# Esquematico.net
KiCad netlist of a schematic drawn in Altium Designer
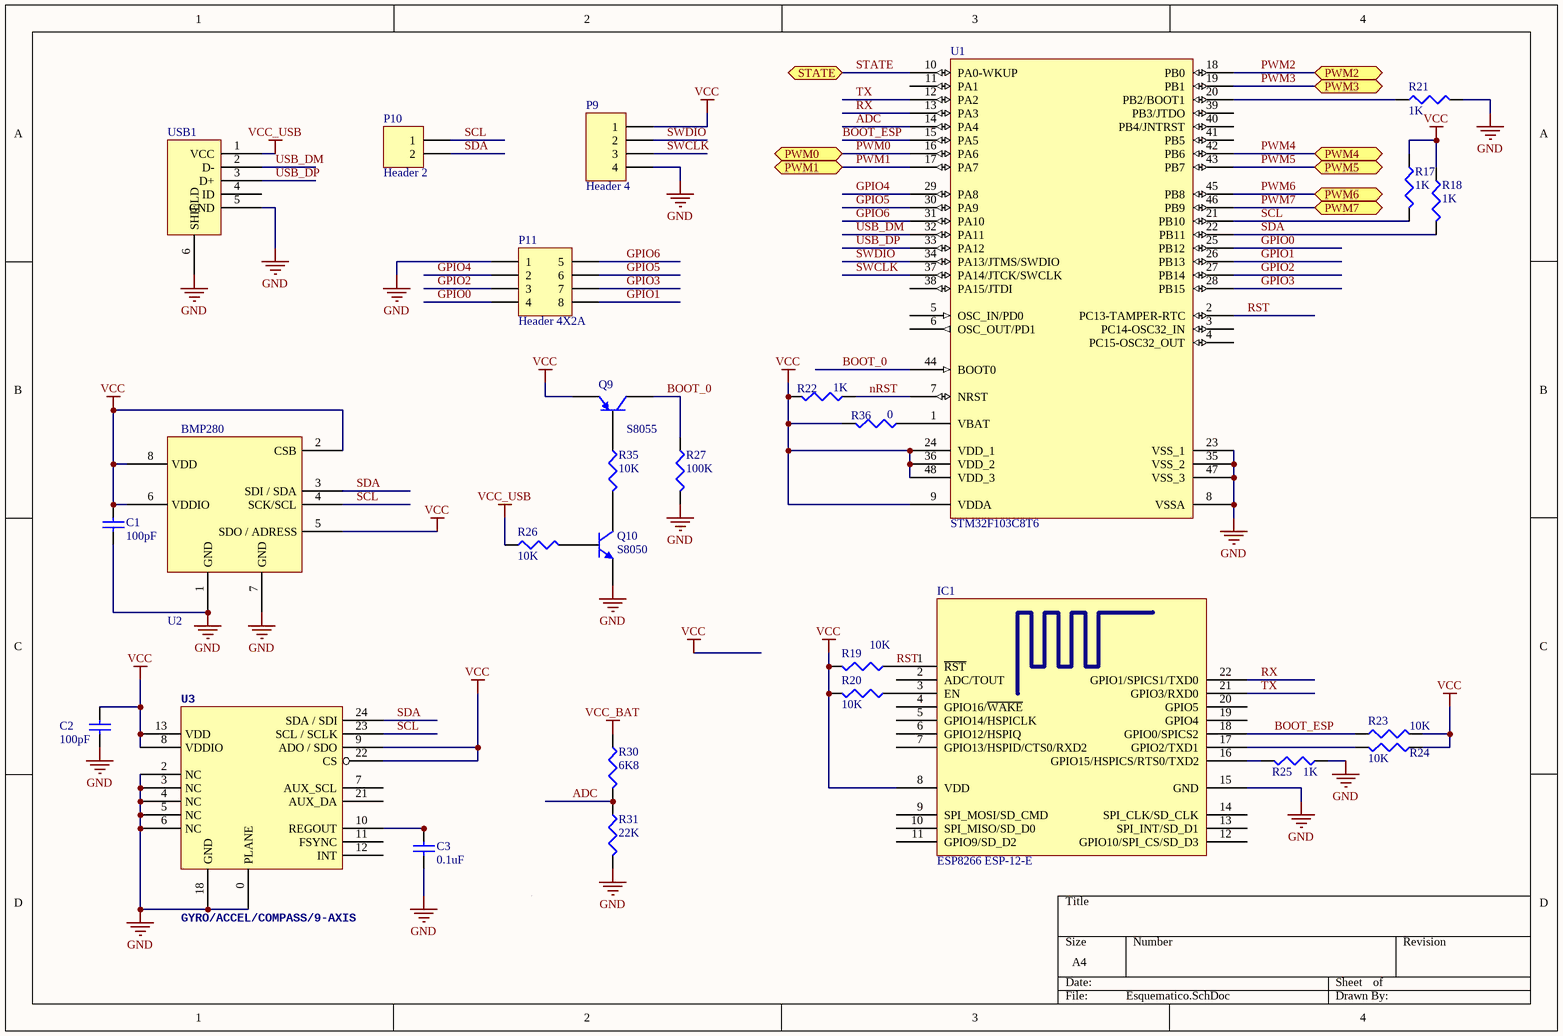
[diagram p0: Esquematico.SchDoc]

(export (version "E")
  (design (tool "Eeschema 10.0.6"))
  (components
    (comp (ref "C1")
      (value "100pF")
      (footprint "Miscellaneous Devices:6-0805_L")
      (description "Capacitor")
      (fields (field (name "Comment") "Cap") (field (name "PUBLISHER") "Altium Limited"))
      (libsource (lib "Miscellaneous Devices") (part "Cap"))
    )
    (comp (ref "C2")
      (value "100pF")
      (footprint "C1206")
      (description "Capacitor")
      (fields (field (name "Comment") "Cap") (field (name "PUBLISHER") "Altium Limited"))
      (libsource (lib "Miscellaneous Devices") (part "Cap"))
    )
    (comp (ref "C3")
      (value "0.1uF")
      (footprint "C1206")
      (description "Capacitor")
      (fields (field (name "Comment") "Cap") (field (name "PUBLISHER") "Altium Limited"))
      (libsource (lib "Miscellaneous Devices") (part "Cap"))
    )
    (comp (ref "IC1")
      (value "ESP8266 ESP-12-E")
      (footprint "ESP8266:ESP8266 ESP-12-E B")
      (libsource (lib "ESP8266") (part "ESP8266 ESP-12-E"))
    )
    (comp (ref "P9")
      (value "Header 4")
      (footprint "HDR1X4")
      (description "Header, 4-Pin")
      (fields (field (name "PUBLISHER") "Altium Limited"))
      (libsource (lib "Miscellaneous Connectors") (part "Header 4"))
    )
    (comp (ref "P10")
      (value "Header 2")
      (footprint "HDR1X2")
      (description "Header, 2-Pin")
      (fields (field (name "PUBLISHER") "Altium Limited"))
      (libsource (lib "Miscellaneous Connectors") (part "Header 2"))
    )
    (comp (ref "P11")
      (value "Header 4X2A")
      (footprint "HDR2X4_CEN")
      (description "Header, 4-Pin, Dual row")
      (fields (field (name "PUBLISHER") "Altium Limited"))
      (libsource (lib "Miscellaneous Connectors") (part "Header 4X2A"))
    )
    (comp (ref "Q9")
      (value "S8055")
      (footprint "SOT23-3")
      (description "PNP SMD General Purpose Amplifier")
      (fields (field (name "PUBLISHER") "Altium Limited"))
      (libsource (lib "Libreria General") (part "S8055"))
    )
    (comp (ref "Q10")
      (value "S8050")
      (footprint "SOT23-3")
      (description "NPN SMD General Purpose Amplifier")
      (fields (field (name "PUBLISHER") "Altium Limited"))
      (libsource (lib "Libreria General") (part "S8050"))
    )
    (comp (ref "R17")
      (value "1K")
      (footprint "C1206")
      (description "Resistor")
      (fields (field (name "Comment") "Res3") (field (name "PUBLISHER") "Altium Limited"))
      (libsource (lib "Miscellaneous Devices") (part "Res3"))
    )
    (comp (ref "R18")
      (value "1K")
      (footprint "C1206")
      (description "Resistor")
      (fields (field (name "Comment") "Res3") (field (name "PUBLISHER") "Altium Limited"))
      (libsource (lib "Miscellaneous Devices") (part "Res3"))
    )
    (comp (ref "R19")
      (value "10K")
      (footprint "6-0805_N")
      (description "Resistor")
      (fields (field (name "Comment") "Res3") (field (name "PUBLISHER") "Altium Limited"))
      (libsource (lib "Miscellaneous Devices") (part "Res3"))
    )
    (comp (ref "R20")
      (value "10K")
      (footprint "6-0805_N")
      (description "Resistor")
      (fields (field (name "Comment") "Res3") (field (name "PUBLISHER") "Altium Limited"))
      (libsource (lib "Miscellaneous Devices") (part "Res3"))
    )
    (comp (ref "R21")
      (value "1K")
      (footprint "C1206")
      (description "Resistor")
      (fields (field (name "Comment") "Res3") (field (name "PUBLISHER") "Altium Limited"))
      (libsource (lib "Miscellaneous Devices") (part "Res3"))
    )
    (comp (ref "R22")
      (value "1K")
      (footprint "6-0805_N")
      (description "Resistor")
      (fields (field (name "Comment") "Res3") (field (name "PUBLISHER") "Altium Limited"))
      (libsource (lib "Miscellaneous Devices") (part "Res3"))
    )
    (comp (ref "R23")
      (value "10K")
      (footprint "6-0805_N")
      (description "Resistor")
      (fields (field (name "Comment") "Res3") (field (name "PUBLISHER") "Altium Limited"))
      (libsource (lib "Miscellaneous Devices") (part "Res3"))
    )
    (comp (ref "R24")
      (value "10K")
      (footprint "6-0805_N")
      (description "Resistor")
      (fields (field (name "Comment") "Res3") (field (name "PUBLISHER") "Altium Limited"))
      (libsource (lib "Miscellaneous Devices") (part "Res3"))
    )
    (comp (ref "R25")
      (value "1K")
      (footprint "6-0805_N")
      (description "Resistor")
      (fields (field (name "Comment") "Res3") (field (name "PUBLISHER") "Altium Limited"))
      (libsource (lib "Miscellaneous Devices") (part "Res3"))
    )
    (comp (ref "R26")
      (value "10K")
      (footprint "6-0805_N")
      (description "Resistor")
      (fields (field (name "Comment") "Res3") (field (name "PUBLISHER") "Altium Limited"))
      (libsource (lib "Miscellaneous Devices") (part "Res3"))
    )
    (comp (ref "R27")
      (value "100K")
      (footprint "6-0805_N")
      (description "Resistor")
      (fields (field (name "Comment") "Res3") (field (name "PUBLISHER") "Altium Limited"))
      (libsource (lib "Miscellaneous Devices") (part "Res3"))
    )
    (comp (ref "R30")
      (value "6K8")
      (footprint "6-0805_N")
      (description "Resistor")
      (fields (field (name "Comment") "Res3") (field (name "PUBLISHER") "Altium Limited"))
      (libsource (lib "Miscellaneous Devices") (part "Res3"))
    )
    (comp (ref "R31")
      (value "22K")
      (footprint "6-0805_N")
      (description "Resistor")
      (fields (field (name "Comment") "Res3") (field (name "PUBLISHER") "Altium Limited"))
      (libsource (lib "Miscellaneous Devices") (part "Res3"))
    )
    (comp (ref "R35")
      (value "10K")
      (footprint "6-0805_N")
      (description "Resistor")
      (fields (field (name "Comment") "Res3") (field (name "PUBLISHER") "Altium Limited"))
      (libsource (lib "Miscellaneous Devices") (part "Res3"))
    )
    (comp (ref "R36")
      (value "0")
      (footprint "6-0805_N")
      (description "Resistor")
      (fields (field (name "Comment") "Res3") (field (name "PUBLISHER") "Altium Limited"))
      (libsource (lib "Miscellaneous Devices") (part "Res3"))
    )
    (comp (ref "U1")
      (value "STM32F103C8T6")
      (footprint "LQFP48_N")
      (description "STM32 ARM-based 32-bit MCU with 64 Kbytes Flash, 48-pin LQFP, Industrial Temperature")
      (fields (field (name "PUBLISHER") "Altium Limited"))
      (libsource (lib "ST Microcontroller 32-Bit STM32") (part "STM32F103C8T6"))
    )
    (comp (ref "U2")
      (value "BMP280")
      (footprint "LGA-8_BMP280(Primary)")
      (description "Barometro")
      (libsource (lib "BMP280") (part "BMP280"))
    )
    (comp (ref "U3")
      (value "GYRO/ACCEL/COMPASS/9-AXIS")
      (footprint "QFN-24/3MM")
      (libsource (lib "MPU-9250") (part "MPU-9250"))
    )
    (comp (ref "USB1")
      (value "Micro_USB")
      (footprint "Micro USB")
      (libsource (lib "Libreria General") (part "Micro_USB"))
    )
  )
  (nets
    (net (code "1") (name "/ADC") (class "Default")
      (node (ref "R30") (pin "2") (pinfunction "2_2") (pintype "passive"))
      (node (ref "R31") (pin "1") (pinfunction "1_1") (pintype "passive"))
      (node (ref "U1") (pin "14") (pinfunction "PA4_14") (pintype "bidirectional"))
    )
    (net (code "2") (name "/BOOT_0") (class "Default")
      (node (ref "Q9") (pin "3") (pinfunction "C_3") (pintype "passive"))
      (node (ref "R27") (pin "1") (pinfunction "1_1") (pintype "passive"))
      (node (ref "U1") (pin "44") (pinfunction "BOOT0_44") (pintype "input"))
    )
    (net (code "3") (name "/BOOT_ESP") (class "Default")
      (node (ref "IC1") (pin "18") (pinfunction "GPIO0/SPICS2_18") (pintype "passive"))
      (node (ref "R23") (pin "1") (pinfunction "1_1") (pintype "passive"))
      (node (ref "U1") (pin "15") (pinfunction "PA5_15") (pintype "bidirectional"))
    )
    (net (code "4") (name "/GPIO0") (class "Default")
      (node (ref "P11") (pin "4") (pinfunction "4_4") (pintype "passive"))
      (node (ref "U1") (pin "25") (pinfunction "PB12_25") (pintype "bidirectional"))
    )
    (net (code "5") (name "/GPIO1") (class "Default")
      (node (ref "P11") (pin "8") (pinfunction "8_8") (pintype "passive"))
      (node (ref "U1") (pin "26") (pinfunction "PB13_26") (pintype "bidirectional"))
    )
    (net (code "6") (name "/GPIO2") (class "Default")
      (node (ref "P11") (pin "3") (pinfunction "3_3") (pintype "passive"))
      (node (ref "U1") (pin "27") (pinfunction "PB14_27") (pintype "bidirectional"))
    )
    (net (code "7") (name "/GPIO3") (class "Default")
      (node (ref "P11") (pin "7") (pinfunction "7_7") (pintype "passive"))
      (node (ref "U1") (pin "28") (pinfunction "PB15_28") (pintype "bidirectional"))
    )
    (net (code "8") (name "/GPIO4") (class "Default")
      (node (ref "P11") (pin "2") (pinfunction "2_2") (pintype "passive"))
      (node (ref "U1") (pin "29") (pinfunction "PA8_29") (pintype "bidirectional"))
    )
    (net (code "9") (name "/GPIO5") (class "Default")
      (node (ref "P11") (pin "6") (pinfunction "6_6") (pintype "passive"))
      (node (ref "U1") (pin "30") (pinfunction "PA9_30") (pintype "bidirectional"))
    )
    (net (code "10") (name "/GPIO6") (class "Default")
      (node (ref "P11") (pin "5") (pinfunction "5_5") (pintype "passive"))
      (node (ref "U1") (pin "31") (pinfunction "PA10_31") (pintype "bidirectional"))
    )
    (net (code "11") (name "/PWM0") (class "Default")
      (node (ref "U1") (pin "16") (pinfunction "PA6_16") (pintype "bidirectional"))
    )
    (net (code "12") (name "/PWM1") (class "Default")
      (node (ref "U1") (pin "17") (pinfunction "PA7_17") (pintype "bidirectional"))
    )
    (net (code "13") (name "/PWM2") (class "Default")
      (node (ref "U1") (pin "18") (pinfunction "PB0_18") (pintype "bidirectional"))
    )
    (net (code "14") (name "/PWM3") (class "Default")
      (node (ref "U1") (pin "19") (pinfunction "PB1_19") (pintype "bidirectional"))
    )
    (net (code "15") (name "/PWM4") (class "Default")
      (node (ref "U1") (pin "42") (pinfunction "PB6_42") (pintype "bidirectional"))
    )
    (net (code "16") (name "/PWM5") (class "Default")
      (node (ref "U1") (pin "43") (pinfunction "PB7_43") (pintype "bidirectional"))
    )
    (net (code "17") (name "/PWM6") (class "Default")
      (node (ref "U1") (pin "45") (pinfunction "PB8_45") (pintype "bidirectional"))
    )
    (net (code "18") (name "/PWM7") (class "Default")
      (node (ref "U1") (pin "46") (pinfunction "PB9_46") (pintype "bidirectional"))
    )
    (net (code "19") (name "/RST") (class "Default")
      (node (ref "IC1") (pin "1") (pinfunction "~{RST}_1") (pintype "passive"))
      (node (ref "R19") (pin "1") (pinfunction "1_1") (pintype "passive"))
      (node (ref "U1") (pin "2") (pinfunction "PC13-TAMPER-RTC_2") (pintype "bidirectional"))
    )
    (net (code "20") (name "/RX") (class "Default")
      (node (ref "IC1") (pin "22") (pinfunction "GPIO1/SPICS1/TXD0_22") (pintype "passive"))
      (node (ref "U1") (pin "13") (pinfunction "PA3_13") (pintype "bidirectional"))
    )
    (net (code "21") (name "/SCL") (class "Default")
      (node (ref "P10") (pin "1") (pinfunction "1_1") (pintype "passive"))
      (node (ref "R17") (pin "2") (pinfunction "2_2") (pintype "passive"))
      (node (ref "U1") (pin "21") (pinfunction "PB10_21") (pintype "bidirectional"))
      (node (ref "U2") (pin "4") (pinfunction "SCK/SCL_4") (pintype "passive"))
      (node (ref "U3") (pin "23") (pinfunction "SCL_/_SCLK_23") (pintype "passive"))
    )
    (net (code "22") (name "/SDA") (class "Default")
      (node (ref "P10") (pin "2") (pinfunction "2_2") (pintype "passive"))
      (node (ref "R18") (pin "2") (pinfunction "2_2") (pintype "passive"))
      (node (ref "U1") (pin "22") (pinfunction "PB11_22") (pintype "bidirectional"))
      (node (ref "U2") (pin "3") (pinfunction "SDI_/_SDA_3") (pintype "passive"))
      (node (ref "U3") (pin "24") (pinfunction "SDA_/_SDI_24") (pintype "passive"))
    )
    (net (code "23") (name "/STATE") (class "Default")
      (node (ref "U1") (pin "10") (pinfunction "PA0-WKUP_10") (pintype "bidirectional"))
    )
    (net (code "24") (name "/SWCLK") (class "Default")
      (node (ref "P9") (pin "3") (pinfunction "3_3") (pintype "passive"))
      (node (ref "U1") (pin "37") (pinfunction "PA14/JTCK/SWCLK_37") (pintype "bidirectional"))
    )
    (net (code "25") (name "/SWDIO") (class "Default")
      (node (ref "P9") (pin "2") (pinfunction "2_2") (pintype "passive"))
      (node (ref "U1") (pin "34") (pinfunction "PA13/JTMS/SWDIO_34") (pintype "bidirectional"))
    )
    (net (code "26") (name "/TX") (class "Default")
      (node (ref "IC1") (pin "21") (pinfunction "GPIO3/RXD0_21") (pintype "passive"))
      (node (ref "U1") (pin "12") (pinfunction "PA2_12") (pintype "bidirectional"))
    )
    (net (code "27") (name "/USB_DM") (class "Default")
      (node (ref "U1") (pin "32") (pinfunction "PA11_32") (pintype "bidirectional"))
      (node (ref "USB1") (pin "2") (pinfunction "D-_2") (pintype "passive"))
    )
    (net (code "28") (name "/USB_DP") (class "Default")
      (node (ref "U1") (pin "33") (pinfunction "PA12_33") (pintype "bidirectional"))
      (node (ref "USB1") (pin "3") (pinfunction "D+_3") (pintype "passive"))
    )
    (net (code "29") (name "/nRST") (class "Default")
      (node (ref "R22") (pin "1") (pinfunction "1_1") (pintype "passive"))
      (node (ref "U1") (pin "7") (pinfunction "NRST_7") (pintype "bidirectional"))
    )
    (net (code "30") (name "GND") (class "Default")
      (node (ref "C1") (pin "1") (pinfunction "1_1") (pintype "passive"))
      (node (ref "C2") (pin "1") (pinfunction "1_1") (pintype "passive"))
      (node (ref "C3") (pin "1") (pinfunction "1_1") (pintype "passive"))
      (node (ref "IC1") (pin "15") (pinfunction "GND_15") (pintype "passive"))
      (node (ref "P11") (pin "1") (pinfunction "1_1") (pintype "passive"))
      (node (ref "P9") (pin "4") (pinfunction "4_4") (pintype "passive"))
      (node (ref "Q10") (pin "2") (pinfunction "E_2") (pintype "passive"))
      (node (ref "R21") (pin "2") (pinfunction "2_2") (pintype "passive"))
      (node (ref "R25") (pin "1") (pinfunction "1_1") (pintype "passive"))
      (node (ref "R27") (pin "2") (pinfunction "2_2") (pintype "passive"))
      (node (ref "R31") (pin "2") (pinfunction "2_2") (pintype "passive"))
      (node (ref "U1") (pin "23") (pinfunction "VSS_1_23") (pintype "power_in"))
      (node (ref "U1") (pin "35") (pinfunction "VSS_2_35") (pintype "power_in"))
      (node (ref "U1") (pin "47") (pinfunction "VSS_3_47") (pintype "power_in"))
      (node (ref "U1") (pin "8") (pinfunction "VSSA_8") (pintype "power_in"))
      (node (ref "U2") (pin "1") (pinfunction "GND_1") (pintype "passive"))
      (node (ref "U2") (pin "7") (pinfunction "GND_7") (pintype "passive"))
      (node (ref "U3") (pin "0") (pinfunction "PLANE_0") (pintype "passive"))
      (node (ref "U3") (pin "18") (pinfunction "GND_18") (pintype "passive"))
      (node (ref "U3") (pin "2") (pinfunction "NC_2") (pintype "passive"))
      (node (ref "U3") (pin "3") (pinfunction "NC_3") (pintype "passive"))
      (node (ref "U3") (pin "4") (pinfunction "NC_4") (pintype "passive"))
      (node (ref "U3") (pin "5") (pinfunction "NC_5") (pintype "passive"))
      (node (ref "U3") (pin "6") (pinfunction "NC_6") (pintype "passive"))
      (node (ref "USB1") (pin "5") (pinfunction "GND_5") (pintype "passive"))
      (node (ref "USB1") (pin "6") (pinfunction "SHIELD_6") (pintype "passive"))
    )
    (net (code "31") (name "Net-(IC1-EN)") (class "Default")
      (node (ref "IC1") (pin "3") (pinfunction "EN_3") (pintype "passive"))
      (node (ref "R20") (pin "1") (pinfunction "1_1") (pintype "passive"))
    )
    (net (code "32") (name "Net-(IC1-GPIO2{slash}TXD1)") (class "Default")
      (node (ref "IC1") (pin "17") (pinfunction "GPIO2/TXD1_17") (pintype "passive"))
      (node (ref "R24") (pin "2") (pinfunction "2_2") (pintype "passive"))
    )
    (net (code "33") (name "Net-(IC1-GPIO15{slash}HSPICS{slash}RTS0{slash}TXD2)") (class "Default")
      (node (ref "IC1") (pin "16") (pinfunction "GPIO15/HSPICS/RTS0/TXD2_16") (pintype "passive"))
      (node (ref "R25") (pin "2") (pinfunction "2_2") (pintype "passive"))
    )
    (net (code "34") (name "Net-(Q9-B)") (class "Default")
      (node (ref "Q9") (pin "1") (pinfunction "B_1") (pintype "passive"))
      (node (ref "R35") (pin "1") (pinfunction "1_1") (pintype "passive"))
    )
    (net (code "35") (name "Net-(Q10-B)") (class "Default")
      (node (ref "Q10") (pin "1") (pinfunction "B_1") (pintype "passive"))
      (node (ref "R26") (pin "2") (pinfunction "2_2") (pintype "passive"))
    )
    (net (code "36") (name "Net-(Q10-C)") (class "Default")
      (node (ref "Q10") (pin "3") (pinfunction "C_3") (pintype "passive"))
      (node (ref "R35") (pin "2") (pinfunction "2_2") (pintype "passive"))
    )
    (net (code "37") (name "Net-(U1-PB2{slash}BOOT1)") (class "Default")
      (node (ref "R21") (pin "1") (pinfunction "1_1") (pintype "passive"))
      (node (ref "U1") (pin "20") (pinfunction "PB2/BOOT1_20") (pintype "bidirectional"))
    )
    (net (code "38") (name "Net-(U1-VBAT)") (class "Default")
      (node (ref "R36") (pin "1") (pinfunction "1_1") (pintype "passive"))
      (node (ref "U1") (pin "1") (pinfunction "VBAT_1") (pintype "power_in"))
    )
    (net (code "39") (name "Net-(U3-REGOUT)") (class "Default")
      (node (ref "C3") (pin "2") (pinfunction "2_2") (pintype "passive"))
      (node (ref "U3") (pin "10") (pinfunction "REGOUT_10") (pintype "passive"))
    )
    (net (code "40") (name "VCC") (class "Default")
      (node (ref "C1") (pin "2") (pinfunction "2_2") (pintype "passive"))
      (node (ref "C2") (pin "2") (pinfunction "2_2") (pintype "passive"))
      (node (ref "IC1") (pin "8") (pinfunction "VDD_8") (pintype "passive"))
      (node (ref "P9") (pin "1") (pinfunction "1_1") (pintype "passive"))
      (node (ref "Q9") (pin "2") (pinfunction "E_2") (pintype "passive"))
      (node (ref "R17") (pin "1") (pinfunction "1_1") (pintype "passive"))
      (node (ref "R18") (pin "1") (pinfunction "1_1") (pintype "passive"))
      (node (ref "R19") (pin "2") (pinfunction "2_2") (pintype "passive"))
      (node (ref "R20") (pin "2") (pinfunction "2_2") (pintype "passive"))
      (node (ref "R22") (pin "2") (pinfunction "2_2") (pintype "passive"))
      (node (ref "R23") (pin "2") (pinfunction "2_2") (pintype "passive"))
      (node (ref "R24") (pin "1") (pinfunction "1_1") (pintype "passive"))
      (node (ref "R36") (pin "2") (pinfunction "2_2") (pintype "passive"))
      (node (ref "U1") (pin "24") (pinfunction "VDD_1_24") (pintype "power_in"))
      (node (ref "U1") (pin "36") (pinfunction "VDD_2_36") (pintype "power_in"))
      (node (ref "U1") (pin "48") (pinfunction "VDD_3_48") (pintype "power_in"))
      (node (ref "U1") (pin "9") (pinfunction "VDDA_9") (pintype "power_in"))
      (node (ref "U2") (pin "2") (pinfunction "CSB_2") (pintype "passive"))
      (node (ref "U2") (pin "5") (pinfunction "SDO_/_ADRESS_5") (pintype "passive"))
      (node (ref "U2") (pin "6") (pinfunction "VDDIO_6") (pintype "passive"))
      (node (ref "U2") (pin "8") (pinfunction "VDD_8") (pintype "passive"))
      (node (ref "U3") (pin "13") (pinfunction "VDD_13") (pintype "passive"))
      (node (ref "U3") (pin "22") (pinfunction "CS_22") (pintype "passive"))
      (node (ref "U3") (pin "8") (pinfunction "VDDIO_8") (pintype "passive"))
      (node (ref "U3") (pin "9") (pinfunction "ADO_/_SDO_9") (pintype "passive"))
    )
    (net (code "41") (name "VCC_BAT") (class "Default")
      (node (ref "R30") (pin "1") (pinfunction "1_1") (pintype "passive"))
    )
    (net (code "42") (name "VCC_USB") (class "Default")
      (node (ref "R26") (pin "1") (pinfunction "1_1") (pintype "passive"))
      (node (ref "USB1") (pin "1") (pinfunction "VCC_1") (pintype "passive"))
    )
    (net (code "43") (name "unconnected-(IC1-ADC{slash}TOUT-Pad2)") (class "Default")
      (node (ref "IC1") (pin "2") (pinfunction "ADC/TOUT_2") (pintype "passive"))
    )
    (net (code "44") (name "unconnected-(IC1-GPIO4-Pad19)") (class "Default")
      (node (ref "IC1") (pin "19") (pinfunction "GPIO4_19") (pintype "passive"))
    )
    (net (code "45") (name "unconnected-(IC1-GPIO5-Pad20)") (class "Default")
      (node (ref "IC1") (pin "20") (pinfunction "GPIO5_20") (pintype "passive"))
    )
    (net (code "46") (name "unconnected-(IC1-GPIO9{slash}SD_D2-Pad11)") (class "Default")
      (node (ref "IC1") (pin "11") (pinfunction "GPIO9/SD_D2_11") (pintype "passive"))
    )
    (net (code "47") (name "unconnected-(IC1-GPIO10{slash}SPI_CS{slash}SD_D3-Pad12)") (class "Default")
      (node (ref "IC1") (pin "12") (pinfunction "GPIO10/SPI_CS/SD_D3_12") (pintype "passive"))
    )
    (net (code "48") (name "unconnected-(IC1-GPIO12{slash}HSPIQ-Pad6)") (class "Default")
      (node (ref "IC1") (pin "6") (pinfunction "GPIO12/HSPIQ_6") (pintype "passive"))
    )
    (net (code "49") (name "unconnected-(IC1-GPIO13{slash}HSPID{slash}CTS0{slash}RXD2-Pad7)") (class "Default")
      (node (ref "IC1") (pin "7") (pinfunction "GPIO13/HSPID/CTS0/RXD2_7") (pintype "passive"))
    )
    (net (code "50") (name "unconnected-(IC1-GPIO14{slash}HSPICLK-Pad5)") (class "Default")
      (node (ref "IC1") (pin "5") (pinfunction "GPIO14/HSPICLK_5") (pintype "passive"))
    )
    (net (code "51") (name "unconnected-(IC1-GPIO16{slash}~{WAKE}-Pad4)") (class "Default")
      (node (ref "IC1") (pin "4") (pinfunction "GPIO16/~{WAKE}_4") (pintype "passive"))
    )
    (net (code "52") (name "unconnected-(IC1-SPI_CLK{slash}SD_CLK-Pad14)") (class "Default")
      (node (ref "IC1") (pin "14") (pinfunction "SPI_CLK/SD_CLK_14") (pintype "passive"))
    )
    (net (code "53") (name "unconnected-(IC1-SPI_INT{slash}SD_D1-Pad13)") (class "Default")
      (node (ref "IC1") (pin "13") (pinfunction "SPI_INT/SD_D1_13") (pintype "passive"))
    )
    (net (code "54") (name "unconnected-(IC1-SPI_MISO{slash}SD_D0-Pad10)") (class "Default")
      (node (ref "IC1") (pin "10") (pinfunction "SPI_MISO/SD_D0_10") (pintype "passive"))
    )
    (net (code "55") (name "unconnected-(IC1-SPI_MOSI{slash}SD_CMD-Pad9)") (class "Default")
      (node (ref "IC1") (pin "9") (pinfunction "SPI_MOSI/SD_CMD_9") (pintype "passive"))
    )
    (net (code "56") (name "unconnected-(U1-OSC_IN{slash}PD0-Pad5)") (class "Default")
      (node (ref "U1") (pin "5") (pinfunction "OSC_IN/PD0_5") (pintype "input"))
    )
    (net (code "57") (name "unconnected-(U1-OSC_OUT{slash}PD1-Pad6)") (class "Default")
      (node (ref "U1") (pin "6") (pinfunction "OSC_OUT/PD1_6") (pintype "output"))
    )
    (net (code "58") (name "unconnected-(U1-PA1-Pad11)") (class "Default")
      (node (ref "U1") (pin "11") (pinfunction "PA1_11") (pintype "bidirectional"))
    )
    (net (code "59") (name "unconnected-(U1-PA15{slash}JTDI-Pad38)") (class "Default")
      (node (ref "U1") (pin "38") (pinfunction "PA15/JTDI_38") (pintype "bidirectional"))
    )
    (net (code "60") (name "unconnected-(U1-PB3{slash}JTDO-Pad39)") (class "Default")
      (node (ref "U1") (pin "39") (pinfunction "PB3/JTDO_39") (pintype "bidirectional"))
    )
    (net (code "61") (name "unconnected-(U1-PB4{slash}JNTRST-Pad40)") (class "Default")
      (node (ref "U1") (pin "40") (pinfunction "PB4/JNTRST_40") (pintype "bidirectional"))
    )
    (net (code "62") (name "unconnected-(U1-PB5-Pad41)") (class "Default")
      (node (ref "U1") (pin "41") (pinfunction "PB5_41") (pintype "bidirectional"))
    )
    (net (code "63") (name "unconnected-(U1-PC14-OSC32_IN-Pad3)") (class "Default")
      (node (ref "U1") (pin "3") (pinfunction "PC14-OSC32_IN_3") (pintype "bidirectional"))
    )
    (net (code "64") (name "unconnected-(U1-PC15-OSC32_OUT-Pad4)") (class "Default")
      (node (ref "U1") (pin "4") (pinfunction "PC15-OSC32_OUT_4") (pintype "bidirectional"))
    )
    (net (code "65") (name "unconnected-(U3-AUX_DA-Pad21)") (class "Default")
      (node (ref "U3") (pin "21") (pinfunction "AUX_DA_21") (pintype "passive"))
    )
    (net (code "66") (name "unconnected-(U3-AUX_SCL-Pad7)") (class "Default")
      (node (ref "U3") (pin "7") (pinfunction "AUX_SCL_7") (pintype "passive"))
    )
    (net (code "67") (name "unconnected-(U3-FSYNC-Pad11)") (class "Default")
      (node (ref "U3") (pin "11") (pinfunction "FSYNC_11") (pintype "passive"))
    )
    (net (code "68") (name "unconnected-(U3-INT-Pad12)") (class "Default")
      (node (ref "U3") (pin "12") (pinfunction "INT_12") (pintype "passive"))
    )
    (net (code "69") (name "unconnected-(USB1-ID-Pad4)") (class "Default")
      (node (ref "USB1") (pin "4") (pinfunction "ID_4") (pintype "passive"))
    )
  )
)
